# InstAmp.net
KiCad netlist of a schematic drawn in EAGLE
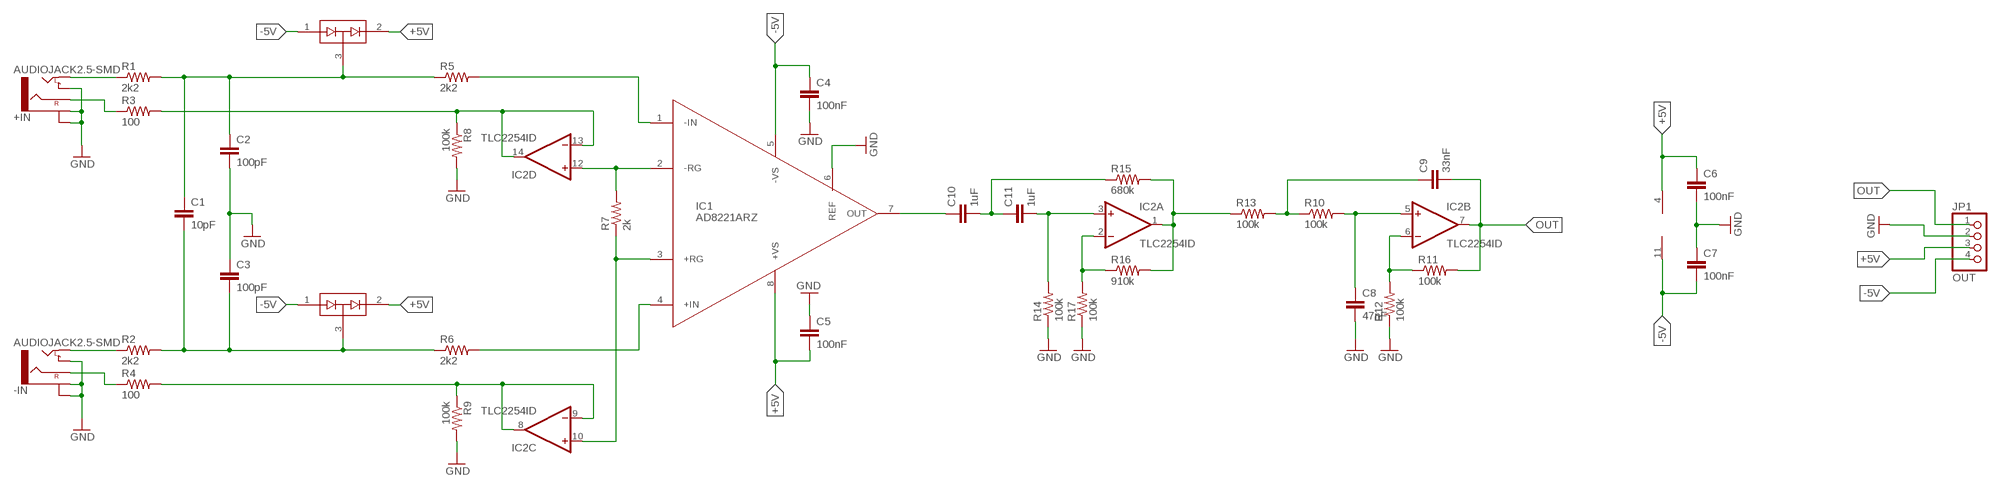
[diagram p0: schematic, sheet 1]

(export (version "E")
  (design (tool "Eeschema 10.0.6"))
  (components
    (comp (ref "+IN")
      (value "AUDIOJACK2.5-SMD")
      (footprint "eagle-import:AUDIOJACK2.5-SMD")
      (libsource (lib "eagle-import") (part "AUDIOJACK2.5-SMD"))
    )
    (comp (ref "-IN")
      (value "AUDIOJACK2.5-SMD")
      (footprint "eagle-import:AUDIOJACK2.5-SMD")
      (libsource (lib "eagle-import") (part "AUDIOJACK2.5-SMD"))
    )
    (comp (ref "C1")
      (value "10pF")
      (footprint "eagle-import:0805")
      (libsource (lib "eagle-import") (part "CAP0805"))
    )
    (comp (ref "C2")
      (value "100pF")
      (footprint "eagle-import:0805")
      (libsource (lib "eagle-import") (part "CAP0805"))
    )
    (comp (ref "C3")
      (value "100pF")
      (footprint "eagle-import:0805")
      (libsource (lib "eagle-import") (part "CAP0805"))
    )
    (comp (ref "C4")
      (value "100nF")
      (footprint "eagle-import:0805")
      (libsource (lib "eagle-import") (part "CAP0805"))
    )
    (comp (ref "C5")
      (value "100nF")
      (footprint "eagle-import:0805")
      (libsource (lib "eagle-import") (part "CAP0805"))
    )
    (comp (ref "C6")
      (value "100nF")
      (footprint "eagle-import:0805")
      (libsource (lib "eagle-import") (part "CAP0805"))
    )
    (comp (ref "C7")
      (value "100nF")
      (footprint "eagle-import:0805")
      (libsource (lib "eagle-import") (part "CAP0805"))
    )
    (comp (ref "C8")
      (value "47nF")
      (footprint "eagle-import:0805")
      (libsource (lib "eagle-import") (part "CAP0805"))
    )
    (comp (ref "C9")
      (value "33nF")
      (footprint "eagle-import:0805")
      (libsource (lib "eagle-import") (part "CAP0805"))
    )
    (comp (ref "C10")
      (value "1uF")
      (footprint "eagle-import:0805")
      (libsource (lib "eagle-import") (part "CAP0805"))
    )
    (comp (ref "C11")
      (value "1uF")
      (footprint "eagle-import:0805")
      (libsource (lib "eagle-import") (part "CAP0805"))
    )
    (comp (ref "D1")
      (value "BAV199")
      (footprint "eagle-import:SOT23")
      (fields (field (name "PROD_ID") "DIO-10647"))
      (libsource (lib "eagle-import") (part "BAV99"))
    )
    (comp (ref "D2")
      (value "BAV199")
      (footprint "eagle-import:SOT23")
      (libsource (lib "eagle-import") (part "BAV99"))
    )
    (comp (ref "IC1")
      (value "AD8221ARZ")
      (footprint "eagle-import:AD8221ARZ")
      (libsource (lib "eagle-import") (part "AD8221ARZ"))
    )
    (comp (ref "IC2")
      (value "TLC2254ID")
      (footprint "eagle-import:SO14")
      (libsource (lib "eagle-import") (part "4AMP_P4+11D"))
    )
    (comp (ref "JP1")
      (value "OUT")
      (footprint "eagle-import:1X04_90")
      (libsource (lib "eagle-import") (part "PINHD-1X4/90"))
    )
    (comp (ref "R1")
      (value "2k2")
      (footprint "eagle-import:0805")
      (libsource (lib "eagle-import") (part "RESISTOR0805-RES"))
    )
    (comp (ref "R2")
      (value "2k2")
      (footprint "eagle-import:0805")
      (libsource (lib "eagle-import") (part "RESISTOR0805-RES"))
    )
    (comp (ref "R3")
      (value "100")
      (footprint "eagle-import:0805")
      (libsource (lib "eagle-import") (part "RESISTOR0805-RES"))
    )
    (comp (ref "R4")
      (value "100")
      (footprint "eagle-import:0805")
      (libsource (lib "eagle-import") (part "RESISTOR0805-RES"))
    )
    (comp (ref "R5")
      (value "2k2")
      (footprint "eagle-import:0805")
      (libsource (lib "eagle-import") (part "RESISTOR0805-RES"))
    )
    (comp (ref "R6")
      (value "2k2")
      (footprint "eagle-import:0805")
      (libsource (lib "eagle-import") (part "RESISTOR0805-RES"))
    )
    (comp (ref "R7")
      (value "2k")
      (footprint "eagle-import:0805")
      (libsource (lib "eagle-import") (part "RESISTOR0805-RES"))
    )
    (comp (ref "R8")
      (value "100k")
      (footprint "eagle-import:0805")
      (libsource (lib "eagle-import") (part "RESISTOR0805-RES"))
    )
    (comp (ref "R9")
      (value "100k")
      (footprint "eagle-import:0805")
      (libsource (lib "eagle-import") (part "RESISTOR0805-RES"))
    )
    (comp (ref "R10")
      (value "100k")
      (footprint "eagle-import:0805")
      (libsource (lib "eagle-import") (part "RESISTOR0805-RES"))
    )
    (comp (ref "R11")
      (value "100k")
      (footprint "eagle-import:0805")
      (libsource (lib "eagle-import") (part "RESISTOR0805-RES"))
    )
    (comp (ref "R12")
      (value "100k")
      (footprint "eagle-import:0805")
      (libsource (lib "eagle-import") (part "RESISTOR0805-RES"))
    )
    (comp (ref "R13")
      (value "100k")
      (footprint "eagle-import:0805")
      (libsource (lib "eagle-import") (part "RESISTOR0805-RES"))
    )
    (comp (ref "R14")
      (value "100k")
      (footprint "eagle-import:0805")
      (libsource (lib "eagle-import") (part "RESISTOR0805-RES"))
    )
    (comp (ref "R15")
      (value "680k")
      (footprint "eagle-import:0805")
      (libsource (lib "eagle-import") (part "RESISTOR0805-RES"))
    )
    (comp (ref "R16")
      (value "910k")
      (footprint "eagle-import:0805")
      (libsource (lib "eagle-import") (part "RESISTOR0805-RES"))
    )
    (comp (ref "R17")
      (value "100k")
      (footprint "eagle-import:0805")
      (libsource (lib "eagle-import") (part "RESISTOR0805-RES"))
    )
  )
  (nets
    (net (code "1") (name "+5V") (class "Default")
      (node (ref "C5") (pin "2") (pinfunction "2_2") (pintype "passive"))
      (node (ref "C6") (pin "1") (pinfunction "1_1") (pintype "passive"))
      (node (ref "D1") (pin "2") (pinfunction "C2_2") (pintype "bidirectional"))
      (node (ref "D2") (pin "2") (pinfunction "C2_2") (pintype "bidirectional"))
      (node (ref "IC1") (pin "8") (pinfunction "+VS_8") (pintype "power_in"))
      (node (ref "IC2") (pin "4") (pinfunction "V+_4") (pintype "power_in"))
      (node (ref "JP1") (pin "3") (pinfunction "3_3") (pintype "passive"))
    )
    (net (code "2") (name "-5V") (class "Default")
      (node (ref "C4") (pin "1") (pinfunction "1_1") (pintype "passive"))
      (node (ref "C7") (pin "2") (pinfunction "2_2") (pintype "passive"))
      (node (ref "D1") (pin "1") (pinfunction "A1_1") (pintype "bidirectional"))
      (node (ref "D2") (pin "1") (pinfunction "A1_1") (pintype "bidirectional"))
      (node (ref "IC1") (pin "5") (pinfunction "-VS_5") (pintype "power_in"))
      (node (ref "IC2") (pin "11") (pinfunction "V-_11") (pintype "power_in"))
      (node (ref "JP1") (pin "4") (pinfunction "4_4") (pintype "passive"))
    )
    (net (code "3") (name "GND") (class "Default")
      (node (ref "+IN") (pin "GND1") (pinfunction "GND1_GND1") (pintype "bidirectional"))
      (node (ref "+IN") (pin "GND2") (pinfunction "GND2_GND2") (pintype "bidirectional"))
      (node (ref "+IN") (pin "SW") (pinfunction "SW_SW") (pintype "bidirectional"))
      (node (ref "-IN") (pin "GND1") (pinfunction "GND1_GND1") (pintype "bidirectional"))
      (node (ref "-IN") (pin "GND2") (pinfunction "GND2_GND2") (pintype "bidirectional"))
      (node (ref "-IN") (pin "SW") (pinfunction "SW_SW") (pintype "bidirectional"))
      (node (ref "C2") (pin "2") (pinfunction "2_2") (pintype "passive"))
      (node (ref "C3") (pin "1") (pinfunction "1_1") (pintype "passive"))
      (node (ref "C4") (pin "2") (pinfunction "2_2") (pintype "passive"))
      (node (ref "C5") (pin "1") (pinfunction "1_1") (pintype "passive"))
      (node (ref "C6") (pin "2") (pinfunction "2_2") (pintype "passive"))
      (node (ref "C7") (pin "1") (pinfunction "1_1") (pintype "passive"))
      (node (ref "C8") (pin "2") (pinfunction "2_2") (pintype "passive"))
      (node (ref "IC1") (pin "6") (pinfunction "REF_6") (pintype "bidirectional"))
      (node (ref "JP1") (pin "2") (pinfunction "2_2") (pintype "passive"))
      (node (ref "R12") (pin "1") (pinfunction "1_1") (pintype "passive"))
      (node (ref "R14") (pin "1") (pinfunction "1_1") (pintype "passive"))
      (node (ref "R17") (pin "1") (pinfunction "1_1") (pintype "passive"))
      (node (ref "R8") (pin "2") (pinfunction "2_2") (pintype "passive"))
      (node (ref "R9") (pin "2") (pinfunction "2_2") (pintype "passive"))
    )
    (net (code "4") (name "Net-(+IN-LEFT)") (class "Default")
      (node (ref "+IN") (pin "L") (pinfunction "LEFT_L") (pintype "bidirectional"))
      (node (ref "R1") (pin "1") (pinfunction "1_1") (pintype "passive"))
    )
    (net (code "5") (name "Net-(+IN-RIGHT)") (class "Default")
      (node (ref "+IN") (pin "R") (pinfunction "RIGHT_R") (pintype "bidirectional"))
      (node (ref "R3") (pin "1") (pinfunction "1_1") (pintype "passive"))
    )
    (net (code "6") (name "Net-(-IN-LEFT)") (class "Default")
      (node (ref "-IN") (pin "L") (pinfunction "LEFT_L") (pintype "bidirectional"))
      (node (ref "R2") (pin "1") (pinfunction "1_1") (pintype "passive"))
    )
    (net (code "7") (name "Net-(-IN-RIGHT)") (class "Default")
      (node (ref "-IN") (pin "R") (pinfunction "RIGHT_R") (pintype "bidirectional"))
      (node (ref "R4") (pin "1") (pinfunction "1_1") (pintype "passive"))
    )
    (net (code "8") (name "Net-(C9-Pad1)") (class "Default")
      (node (ref "C9") (pin "1") (pinfunction "1_1") (pintype "passive"))
      (node (ref "R10") (pin "1") (pinfunction "1_1") (pintype "passive"))
      (node (ref "R13") (pin "2") (pinfunction "2_2") (pintype "passive"))
    )
    (net (code "9") (name "Net-(C10-Pad2)") (class "Default")
      (node (ref "C10") (pin "2") (pinfunction "2_2") (pintype "passive"))
      (node (ref "C11") (pin "1") (pinfunction "1_1") (pintype "passive"))
      (node (ref "R15") (pin "1") (pinfunction "1_1") (pintype "passive"))
    )
    (net (code "10") (name "Net-(D1-COM)") (class "Default")
      (node (ref "C1") (pin "1") (pinfunction "1_1") (pintype "passive"))
      (node (ref "C2") (pin "1") (pinfunction "1_1") (pintype "passive"))
      (node (ref "D1") (pin "3") (pinfunction "COM_3") (pintype "bidirectional"))
      (node (ref "R1") (pin "2") (pinfunction "2_2") (pintype "passive"))
      (node (ref "R5") (pin "1") (pinfunction "1_1") (pintype "passive"))
    )
    (net (code "11") (name "Net-(D2-COM)") (class "Default")
      (node (ref "C1") (pin "2") (pinfunction "2_2") (pintype "passive"))
      (node (ref "C3") (pin "2") (pinfunction "2_2") (pintype "passive"))
      (node (ref "D2") (pin "3") (pinfunction "COM_3") (pintype "bidirectional"))
      (node (ref "R2") (pin "2") (pinfunction "2_2") (pintype "passive"))
      (node (ref "R6") (pin "1") (pinfunction "1_1") (pintype "passive"))
    )
    (net (code "12") (name "Net-(IC1-+IN)") (class "Default")
      (node (ref "IC1") (pin "4") (pinfunction "+IN_4") (pintype "bidirectional"))
      (node (ref "R6") (pin "2") (pinfunction "2_2") (pintype "passive"))
    )
    (net (code "13") (name "Net-(IC1-+RG)") (class "Default")
      (node (ref "IC1") (pin "3") (pinfunction "+RG_3") (pintype "bidirectional"))
      (node (ref "IC2") (pin "10") (pinfunction "+IN_10") (pintype "input"))
      (node (ref "R7") (pin "1") (pinfunction "1_1") (pintype "passive"))
    )
    (net (code "14") (name "Net-(IC1--IN)") (class "Default")
      (node (ref "IC1") (pin "1") (pinfunction "-IN_1") (pintype "bidirectional"))
      (node (ref "R5") (pin "2") (pinfunction "2_2") (pintype "passive"))
    )
    (net (code "15") (name "Net-(IC1--RG)") (class "Default")
      (node (ref "IC1") (pin "2") (pinfunction "-RG_2") (pintype "bidirectional"))
      (node (ref "IC2") (pin "12") (pinfunction "+IN_12") (pintype "input"))
      (node (ref "R7") (pin "2") (pinfunction "2_2") (pintype "passive"))
    )
    (net (code "16") (name "Net-(IC1-OUT)") (class "Default")
      (node (ref "C10") (pin "1") (pinfunction "1_1") (pintype "passive"))
      (node (ref "IC1") (pin "7") (pinfunction "OUT_7") (pintype "bidirectional"))
    )
    (net (code "17") (name "Net-(IC2A-+IN)") (class "Default")
      (node (ref "C11") (pin "2") (pinfunction "2_2") (pintype "passive"))
      (node (ref "IC2") (pin "3") (pinfunction "+IN_3") (pintype "input"))
      (node (ref "R14") (pin "2") (pinfunction "2_2") (pintype "passive"))
    )
    (net (code "18") (name "Net-(IC2A--IN)") (class "Default")
      (node (ref "IC2") (pin "2") (pinfunction "-IN_2") (pintype "input"))
      (node (ref "R16") (pin "1") (pinfunction "1_1") (pintype "passive"))
      (node (ref "R17") (pin "2") (pinfunction "2_2") (pintype "passive"))
    )
    (net (code "19") (name "Net-(IC2A-OUT)") (class "Default")
      (node (ref "IC2") (pin "1") (pinfunction "OUT_1") (pintype "output"))
      (node (ref "R13") (pin "1") (pinfunction "1_1") (pintype "passive"))
      (node (ref "R15") (pin "2") (pinfunction "2_2") (pintype "passive"))
      (node (ref "R16") (pin "2") (pinfunction "2_2") (pintype "passive"))
    )
    (net (code "20") (name "Net-(IC2B-+IN)") (class "Default")
      (node (ref "C8") (pin "1") (pinfunction "1_1") (pintype "passive"))
      (node (ref "IC2") (pin "5") (pinfunction "+IN_5") (pintype "input"))
      (node (ref "R10") (pin "2") (pinfunction "2_2") (pintype "passive"))
    )
    (net (code "21") (name "Net-(IC2B--IN)") (class "Default")
      (node (ref "IC2") (pin "6") (pinfunction "-IN_6") (pintype "input"))
      (node (ref "R11") (pin "1") (pinfunction "1_1") (pintype "passive"))
      (node (ref "R12") (pin "2") (pinfunction "2_2") (pintype "passive"))
    )
    (net (code "22") (name "Net-(IC2C--IN)") (class "Default")
      (node (ref "IC2") (pin "8") (pinfunction "OUT_8") (pintype "output"))
      (node (ref "IC2") (pin "9") (pinfunction "-IN_9") (pintype "input"))
      (node (ref "R4") (pin "2") (pinfunction "2_2") (pintype "passive"))
      (node (ref "R9") (pin "1") (pinfunction "1_1") (pintype "passive"))
    )
    (net (code "23") (name "Net-(IC2D--IN)") (class "Default")
      (node (ref "IC2") (pin "13") (pinfunction "-IN_13") (pintype "input"))
      (node (ref "IC2") (pin "14") (pinfunction "OUT_14") (pintype "output"))
      (node (ref "R3") (pin "2") (pinfunction "2_2") (pintype "passive"))
      (node (ref "R8") (pin "1") (pinfunction "1_1") (pintype "passive"))
    )
    (net (code "24") (name "OUT") (class "Default")
      (node (ref "C9") (pin "2") (pinfunction "2_2") (pintype "passive"))
      (node (ref "IC2") (pin "7") (pinfunction "OUT_7") (pintype "output"))
      (node (ref "JP1") (pin "1") (pinfunction "1_1") (pintype "passive"))
      (node (ref "R11") (pin "2") (pinfunction "2_2") (pintype "passive"))
    )
  )
)
